# POWER_SHEET.net
KiCad netlist of a schematic drawn in Altium Designer
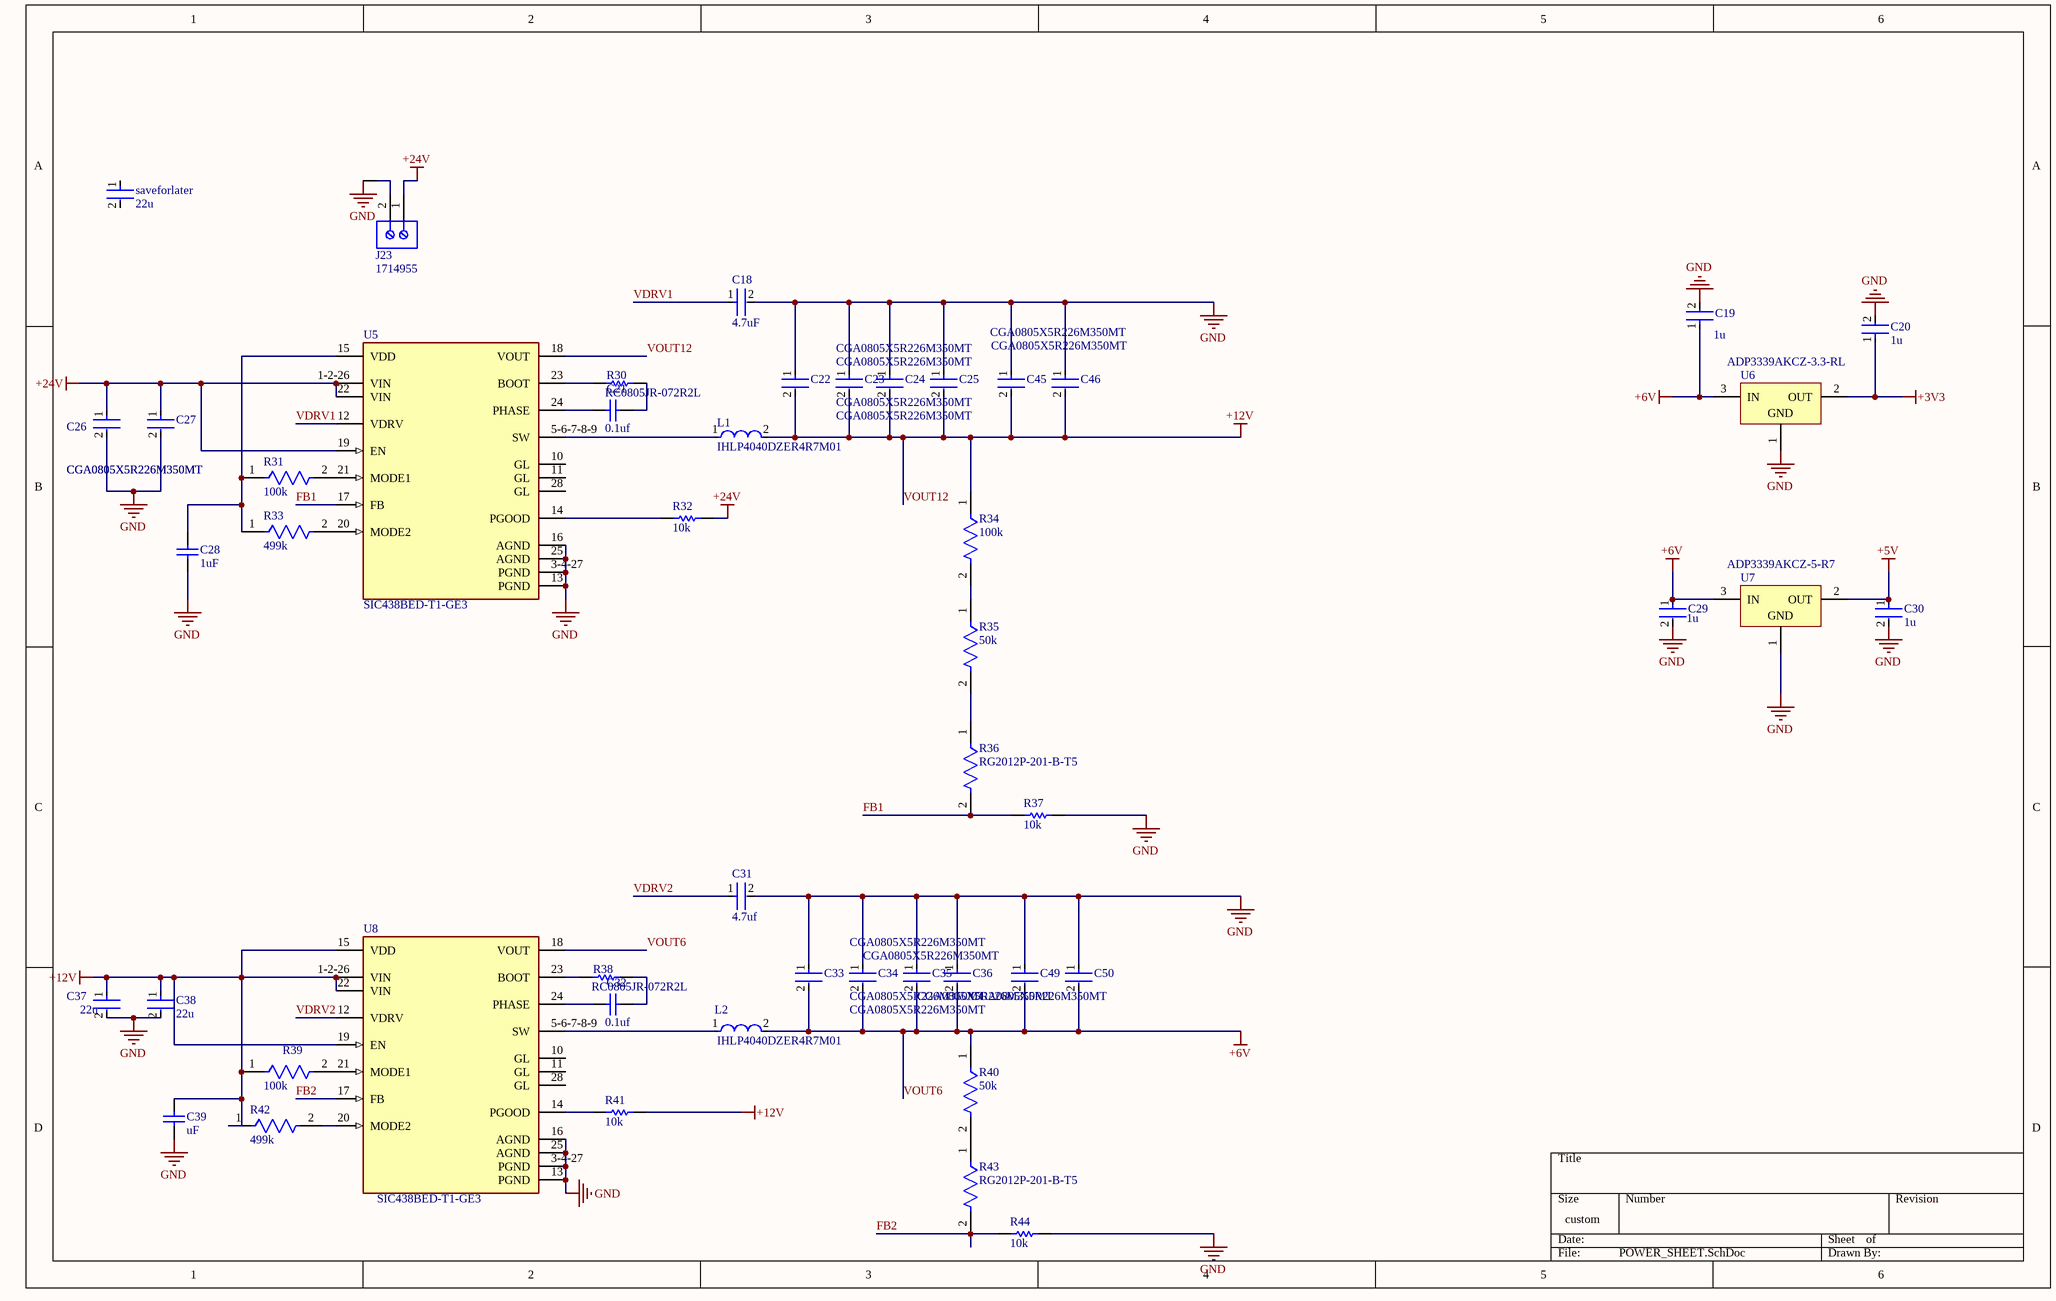
[diagram p0: POWER_SHEET.SchDoc]

(export (version "E")
  (design (tool "Eeschema 10.0.6"))
  (components
    (comp (ref "C18")
      (value "4.7uF")
      (footprint "FP-CL21-IPC_A")
      (description "CL21 Series 0805 4.7uF 25V ±10% Tolerance X5R Multilayer Ceramic Chip Capacitor")
      (fields (field (name "TOLERANCE") "10%"))
      (libsource (lib "Altium Content Vault") (part "b4654b650e69147ec39a6b967a45e02"))
    )
    (comp (ref "C19")
      (value "1u")
      (footprint "FP-CL21-IPC_A")
      (description "CL21 Series 0805 1uF 16V ±10% Tolerance X7R Multilayer Ceramic Chip Capacitor")
      (fields (field (name "TOLERANCE") "10%") (field (name "VOLTAGE") "16V"))
      (libsource (lib "Altium Content Vault") (part "b4654b650e69147ec39a6b967a45e02"))
    )
    (comp (ref "C20")
      (value "1u")
      (footprint "FP-CL21-IPC_A")
      (description "CL21 Series 0805 1uF 16V ±10% Tolerance X7R Multilayer Ceramic Chip Capacitor")
      (fields (field (name "TOLERANCE") "10%") (field (name "VOLTAGE") "16V"))
      (libsource (lib "Altium Content Vault") (part "b4654b650e69147ec39a6b967a45e02"))
    )
    (comp (ref "C21")
      (value "0.1uf")
      (footprint "CAPC2013X94X50LL20T25")
      (fields
        (field (name "MANUFACTURER") "AVX Interconnect / Elco")
        (field (name "PART NUMBER") "08055A6R0CAT2A")
      )
      (libsource (lib "Altium Content Vault") (part "CAP"))
    )
    (comp (ref "C22")
      (value "CGA0805X5R226M350MT")
      (footprint "FP-GRM21B-0_2-e0_2_0_7-IPC_A")
      (description "Chip Multilayer Ceramic Capacitors for General Purpose, 0805, 100uF, X5R, 15%, 20%, 6.3V")
      (fields (field (name "TOLERANCE") "20%"))
      (libsource (lib "Altium Content Vault") (part "b4654b650e69147ec39a6b967a45e02"))
    )
    (comp (ref "C23")
      (value "CGA0805X5R226M350MT")
      (footprint "FP-GRM21B-0_2-e0_2_0_7-IPC_A")
      (description "Chip Multilayer Ceramic Capacitors for General Purpose, 0805, 100uF, X5R, 15%, 20%, 6.3V")
      (fields (field (name "TOLERANCE") "20%"))
      (libsource (lib "Altium Content Vault") (part "b4654b650e69147ec39a6b967a45e02"))
    )
    (comp (ref "C24")
      (value "CGA0805X5R226M350MT")
      (footprint "FP-GRM21B-0_2-e0_2_0_7-IPC_A")
      (description "Chip Multilayer Ceramic Capacitors for General Purpose, 0805, 100uF, X5R, 15%, 20%, 6.3V")
      (fields (field (name "TOLERANCE") "20%"))
      (libsource (lib "Altium Content Vault") (part "b4654b650e69147ec39a6b967a45e02"))
    )
    (comp (ref "C25")
      (value "CGA0805X5R226M350MT")
      (footprint "FP-GRM21B-0_2-e0_2_0_7-IPC_A")
      (description "Chip Multilayer Ceramic Capacitors for General Purpose, 0805, 100uF, X5R, 15%, 20%, 6.3V")
      (fields (field (name "TOLERANCE") "20%"))
      (libsource (lib "Altium Content Vault") (part "b4654b650e69147ec39a6b967a45e02"))
    )
    (comp (ref "C26")
      (value "CGA0805X5R226M350MT")
      (footprint "FP-GRM21B-0_2-e0_2_0_7-IPC_A")
      (description "Chip Multilayer Ceramic Capacitors for General Purpose, 0805, 100uF, X5R, 15%, 20%, 6.3V")
      (fields (field (name "TOLERANCE") "20%"))
      (libsource (lib "Altium Content Vault") (part "b4654b650e69147ec39a6b967a45e02"))
    )
    (comp (ref "C27")
      (value "CGA0805X5R226M350MT")
      (footprint "FP-GRM21B-0_2-e0_2_0_7-IPC_A")
      (description "Chip Multilayer Ceramic Capacitors for General Purpose, 0805, 100uF, X5R, 15%, 20%, 6.3V")
      (fields (field (name "TOLERANCE") "20%"))
      (libsource (lib "Altium Content Vault") (part "b4654b650e69147ec39a6b967a45e02"))
    )
    (comp (ref "C28")
      (value "1uF")
      (footprint "CAPC2013X94X50ML25T25")
      (fields
        (field (name "MANUFACTURER") "AVX Interconnect / Elco")
        (field (name "PART NUMBER") "LD055C224KAB2A")
      )
      (libsource (lib "Altium Content Vault") (part "CAP"))
    )
    (comp (ref "C29")
      (value "1u")
      (footprint "FP-CL21-IPC_A")
      (description "CL21 Series 0805 1uF 16V ±10% Tolerance X7R Multilayer Ceramic Chip Capacitor")
      (fields (field (name "TOLERANCE") "10%") (field (name "VOLTAGE") "16V"))
      (libsource (lib "Altium Content Vault") (part "b4654b650e69147ec39a6b967a45e02"))
    )
    (comp (ref "C30")
      (value "1u")
      (footprint "FP-CL21-IPC_A")
      (description "CL21 Series 0805 1uF 16V ±10% Tolerance X7R Multilayer Ceramic Chip Capacitor")
      (fields (field (name "TOLERANCE") "10%") (field (name "VOLTAGE") "16V"))
      (libsource (lib "Altium Content Vault") (part "b4654b650e69147ec39a6b967a45e02"))
    )
    (comp (ref "C31")
      (value "4.7uf")
      (footprint "FP-CL21-IPC_A")
      (description "CL21 Series 0805 4.7uF 25V ±10% Tolerance X5R Multilayer Ceramic Chip Capacitor")
      (fields (field (name "TOLERANCE") "10%"))
      (libsource (lib "Altium Content Vault") (part "b4654b650e69147ec39a6b967a45e02"))
    )
    (comp (ref "C32")
      (value "0.1uf")
      (footprint "CAPC2013X94X50LL20T25")
      (fields
        (field (name "MANUFACTURER") "AVX Interconnect / Elco")
        (field (name "PART NUMBER") "08055A6R0CAT2A")
      )
      (libsource (lib "Altium Content Vault") (part "CAP"))
    )
    (comp (ref "C33")
      (value "CGA0805X5R226M350MT")
      (footprint "FP-GRM21B-0_2-e0_2_0_7-IPC_A")
      (description "Chip Multilayer Ceramic Capacitors for General Purpose, 0805, 100uF, X5R, 15%, 20%, 6.3V")
      (fields (field (name "TOLERANCE") "20%"))
      (libsource (lib "Altium Content Vault") (part "b4654b650e69147ec39a6b967a45e02"))
    )
    (comp (ref "C34")
      (value "CGA0805X5R226M350MT")
      (footprint "FP-GRM21B-0_2-e0_2_0_7-IPC_A")
      (description "Chip Multilayer Ceramic Capacitors for General Purpose, 0805, 100uF, X5R, 15%, 20%, 6.3V")
      (fields (field (name "TOLERANCE") "20%"))
      (libsource (lib "Altium Content Vault") (part "b4654b650e69147ec39a6b967a45e02"))
    )
    (comp (ref "C35")
      (value "CGA0805X5R226M350MT")
      (footprint "FP-GRM21B-0_2-e0_2_0_7-IPC_A")
      (description "Chip Multilayer Ceramic Capacitors for General Purpose, 0805, 100uF, X5R, 15%, 20%, 6.3V")
      (fields (field (name "TOLERANCE") "20%"))
      (libsource (lib "Altium Content Vault") (part "b4654b650e69147ec39a6b967a45e02"))
    )
    (comp (ref "C36")
      (value "CGA0805X5R226M350MT")
      (footprint "FP-GRM21B-0_2-e0_2_0_7-IPC_A")
      (description "Chip Multilayer Ceramic Capacitors for General Purpose, 0805, 100uF, X5R, 15%, 20%, 6.3V")
      (fields (field (name "TOLERANCE") "20%"))
      (libsource (lib "Altium Content Vault") (part "b4654b650e69147ec39a6b967a45e02"))
    )
    (comp (ref "C37")
      (value "22u")
      (footprint "FP-CL21-IPC_C")
      (description "CL21 Series 0805 22uF 25V ±20% Tolerance X5R Multilayer Ceramic Chip Capacitor")
      (libsource (lib "Altium Content Vault") (part "b4654b650e69147ec39a6b967a45e02"))
    )
    (comp (ref "C38")
      (value "22u")
      (footprint "FP-CL21-IPC_C")
      (description "CL21 Series 0805 22uF 25V ±20% Tolerance X5R Multilayer Ceramic Chip Capacitor")
      (libsource (lib "Altium Content Vault") (part "b4654b650e69147ec39a6b967a45e02"))
    )
    (comp (ref "C39")
      (value "uF")
      (footprint "CAPC2013X94X50ML25T25")
      (fields
        (field (name "MANUFACTURER") "AVX Interconnect / Elco")
        (field (name "PART NUMBER") "LD055C224KAB2A")
      )
      (libsource (lib "Altium Content Vault") (part "CAP"))
    )
    (comp (ref "C45")
      (value "CGA0805X5R226M350MT")
      (footprint "FP-GRM21B-0_2-e0_2_0_7-IPC_A")
      (description "Chip Multilayer Ceramic Capacitors for General Purpose, 0805, 100uF, X5R, 15%, 20%, 6.3V")
      (fields (field (name "TOLERANCE") "20%"))
      (libsource (lib "Altium Content Vault") (part "b4654b650e69147ec39a6b967a45e02"))
    )
    (comp (ref "C46")
      (value "CGA0805X5R226M350MT")
      (footprint "FP-GRM21B-0_2-e0_2_0_7-IPC_A")
      (description "Chip Multilayer Ceramic Capacitors for General Purpose, 0805, 100uF, X5R, 15%, 20%, 6.3V")
      (fields (field (name "TOLERANCE") "20%"))
      (libsource (lib "Altium Content Vault") (part "b4654b650e69147ec39a6b967a45e02"))
    )
    (comp (ref "C49")
      (value "CGA0805X5R226M350MT")
      (footprint "FP-GRM21B-0_2-e0_2_0_7-IPC_A")
      (description "Chip Multilayer Ceramic Capacitors for General Purpose, 0805, 100uF, X5R, 15%, 20%, 6.3V")
      (fields (field (name "TOLERANCE") "20%"))
      (libsource (lib "Altium Content Vault") (part "b4654b650e69147ec39a6b967a45e02"))
    )
    (comp (ref "C50")
      (value "CGA0805X5R226M350MT")
      (footprint "FP-GRM21B-0_2-e0_2_0_7-IPC_A")
      (description "Chip Multilayer Ceramic Capacitors for General Purpose, 0805, 100uF, X5R, 15%, 20%, 6.3V")
      (fields (field (name "TOLERANCE") "20%"))
      (libsource (lib "Altium Content Vault") (part "b4654b650e69147ec39a6b967a45e02"))
    )
    (comp (ref "J23")
      (value "1714955")
      (footprint "PHOE-1714955_V")
      (description "PC Terminal Block, Pitch 6.35 mm, 1 x 2 Position, Height 21.5 mm, Tail Lenght 5.1 mm, RoHS, Bulk")
      (fields (field (name "MANUFACTURER") "Phoenix Contact"))
      (libsource (lib "Altium Content Vault") (part "CN-1P-F-TB2"))
    )
    (comp (ref "L1")
      (value "IHLP4040DZER4R7M01")
      (footprint "FP-IHLP-4040DZ-FP_3_124x3-MFG")
      (description "Commercial Inductors, High Saturation Series 4.7uH 9.5A 16.5mΩ 20%")
      (fields (field (name "TOLERANCE") "20%"))
      (libsource (lib "Altium Content Vault") (part "725321dda6339637d4d059423bc1c3c"))
    )
    (comp (ref "L2")
      (value "IHLP4040DZER4R7M01")
      (footprint "FP-IHLP-4040DZ-FP_3_124x3-MFG")
      (description "Commercial Inductors, High Saturation Series 4.7uH 9.5A 16.5mΩ 20%")
      (fields (field (name "TOLERANCE") "20%"))
      (libsource (lib "Altium Content Vault") (part "725321dda6339637d4d059423bc1c3c"))
    )
    (comp (ref "R30")
      (value "RC0805JR-072R2L")
      (footprint "RESC2013X60X35LL10T20")
      (fields (field (name "MANUFACTURER") "Yageo"))
      (libsource (lib "Altium Content Vault") (part "RES"))
    )
    (comp (ref "R31")
      (value "100k")
      (footprint "FP-ESR10-MFG")
      (description "100kΩ ±5% 0.4W 0805 Anti-Surge Chip Resistor AEC-Q200")
      (fields (field (name "TOLERANCE") "5%"))
      (libsource (lib "Altium Content Vault") (part "1029c3af85768c4190bb7ad29bc67b5"))
    )
    (comp (ref "R32")
      (value "10k")
      (footprint "RESC2013X60X40LL20T25_A")
      (fields (field (name "TOLERANCE") "0.1%") (field (name "MANUFACTURER") "Panasonic"))
      (libsource (lib "Altium Content Vault") (part "RES-2"))
    )
    (comp (ref "R33")
      (value "499k")
      (footprint "FP-RT0805-MFG")
      (description "RES SMD 332K OHM 1% 1/8W 0805")
      (fields
        (field (name "OCTOPART") "https://octopart.com/rt0805fre07332kl-yageo-1277672")
        (field (name "TOLERANCE") "0.0001")
      )
      (libsource (lib "Altium Content Vault") (part "1029c3af85768c4190bb7ad29bc67b5"))
    )
    (comp (ref "R34")
      (value "100k")
      (footprint "FP-ESR10-MFG")
      (description "100kΩ ±5% 0.4W 0805 Anti-Surge Chip Resistor AEC-Q200")
      (fields (field (name "TOLERANCE") "5%"))
      (libsource (lib "Altium Content Vault") (part "1029c3af85768c4190bb7ad29bc67b5"))
    )
    (comp (ref "R35")
      (value "50k")
      (footprint "FP-PNM0805-MFG")
      (description "RES SMD 50K OHM 0.1% 1/5W 0805")
      (fields (field (name "TOLERANCE") "0.1%"))
      (libsource (lib "Altium Content Vault") (part "1029c3af85768c4190bb7ad29bc67b5"))
    )
    (comp (ref "R36")
      (value "RG2012P-201-B-T5")
      (footprint "FP-RG2012-IPC_A")
      (description "Automotive Metal Thin Film Chip Resistor, 0805, 200Ω, 0.1%, 25ppm/°C, 0.125W, 150V")
      (fields (field (name "TOLERANCE") "0.1%"))
      (libsource (lib "Altium Content Vault") (part "1029c3af85768c4190bb7ad29bc67b5"))
    )
    (comp (ref "R37")
      (value "10k")
      (footprint "RESC2013X60X40LL20T25_A")
      (fields (field (name "TOLERANCE") "0.1%") (field (name "MANUFACTURER") "Panasonic"))
      (libsource (lib "Altium Content Vault") (part "RES-2"))
    )
    (comp (ref "R38")
      (value "RC0805JR-072R2L")
      (footprint "RESC2013X60X35LL10T20")
      (fields (field (name "MANUFACTURER") "Yageo"))
      (libsource (lib "Altium Content Vault") (part "RES"))
    )
    (comp (ref "R39")
      (value "100k")
      (footprint "FP-ESR10-MFG")
      (description "100kΩ ±5% 0.4W 0805 Anti-Surge Chip Resistor AEC-Q200")
      (fields (field (name "TOLERANCE") "5%"))
      (libsource (lib "Altium Content Vault") (part "1029c3af85768c4190bb7ad29bc67b5"))
    )
    (comp (ref "R40")
      (value "50k")
      (footprint "FP-PNM0805-MFG")
      (description "RES SMD 50K OHM 0.1% 1/5W 0805")
      (fields (field (name "TOLERANCE") "0.1%"))
      (libsource (lib "Altium Content Vault") (part "1029c3af85768c4190bb7ad29bc67b5"))
    )
    (comp (ref "R41")
      (value "10k")
      (footprint "RESC2013X60X40LL20T25_A")
      (fields (field (name "TOLERANCE") "0.1%") (field (name "MANUFACTURER") "Panasonic"))
      (libsource (lib "Altium Content Vault") (part "RES-2"))
    )
    (comp (ref "R42")
      (value "499k")
      (footprint "FP-RT0805-MFG")
      (description "RES SMD 332K OHM 1% 1/8W 0805")
      (fields
        (field (name "OCTOPART") "https://octopart.com/rt0805fre07332kl-yageo-1277672")
        (field (name "TOLERANCE") "0.0001")
      )
      (libsource (lib "Altium Content Vault") (part "1029c3af85768c4190bb7ad29bc67b5"))
    )
    (comp (ref "R43")
      (value "RG2012P-201-B-T5")
      (footprint "FP-RG2012-IPC_A")
      (description "Automotive Metal Thin Film Chip Resistor, 0805, 200Ω, 0.1%, 25ppm/°C, 0.125W, 150V")
      (fields (field (name "TOLERANCE") "0.1%"))
      (libsource (lib "Altium Content Vault") (part "1029c3af85768c4190bb7ad29bc67b5"))
    )
    (comp (ref "R44")
      (value "10k")
      (footprint "RESC2013X60X40LL20T25_A")
      (fields (field (name "TOLERANCE") "0.1%") (field (name "MANUFACTURER") "Panasonic"))
      (libsource (lib "Altium Content Vault") (part "RES-2"))
    )
    (comp (ref "saveforlater")
      (value "22u")
      (footprint "FP-CL21-IPC_C")
      (description "CL21 Series 0805 22uF 25V ±20% Tolerance X5R Multilayer Ceramic Chip Capacitor")
      (libsource (lib "Altium Content Vault") (part "b4654b650e69147ec39a6b967a45e02"))
    )
    (comp (ref "U5")
      (value "SIC438BED-T1-GE3")
      (footprint "FP-T22-0442-MFG")
      (libsource (lib "Altium Content Vault") (part "ab0672d4ef5f671f4783a9619e06a30"))
    )
    (comp (ref "U6")
      (value "ADP3339AKCZ-3.3-RL")
      (footprint "ADI-KC-3_N")
      (fields (field (name "MANUFACTURER") "Analog Devices"))
      (libsource (lib "Altium Content Vault") (part "ADI-ADP3339-KC-3"))
    )
    (comp (ref "U7")
      (value "ADP3339AKCZ-5-R7")
      (footprint "ADI-KC-3_N")
      (fields (field (name "MANUFACTURER") "Analog Devices"))
      (libsource (lib "Altium Content Vault") (part "ADI-ADP3339-KC-3"))
    )
    (comp (ref "U8")
      (value "SIC438BED-T1-GE3")
      (footprint "FP-T22-0442-MFG")
      (libsource (lib "Altium Content Vault") (part "ab0672d4ef5f671f4783a9619e06a30"))
    )
  )
  (nets
    (net (code "1") (name "+3V3") (class "Default")
      (node (ref "C20") (pin "1") (pinfunction "1_1") (pintype "passive"))
      (node (ref "U6") (pin "2") (pinfunction "OUT_2") (pintype "power_in"))
    )
    (net (code "2") (name "+5V") (class "Default")
      (node (ref "C30") (pin "1") (pinfunction "1_1") (pintype "passive"))
      (node (ref "U7") (pin "2") (pinfunction "OUT_2") (pintype "power_in"))
    )
    (net (code "3") (name "+6V") (class "Default")
      (node (ref "C19") (pin "1") (pinfunction "1_1") (pintype "passive"))
      (node (ref "C29") (pin "1") (pinfunction "1_1") (pintype "passive"))
      (node (ref "C33") (pin "2") (pinfunction "2_2") (pintype "passive"))
      (node (ref "C34") (pin "2") (pinfunction "2_2") (pintype "passive"))
      (node (ref "C35") (pin "2") (pinfunction "2_2") (pintype "passive"))
      (node (ref "C36") (pin "2") (pinfunction "2_2") (pintype "passive"))
      (node (ref "C49") (pin "2") (pinfunction "2_2") (pintype "passive"))
      (node (ref "C50") (pin "2") (pinfunction "2_2") (pintype "passive"))
      (node (ref "L2") (pin "2") (pinfunction "2_2") (pintype "passive"))
      (node (ref "R40") (pin "1") (pinfunction "1_1") (pintype "passive"))
      (node (ref "U6") (pin "3") (pinfunction "IN_3") (pintype "power_in"))
      (node (ref "U7") (pin "3") (pinfunction "IN_3") (pintype "power_in"))
      (node (ref "U8") (pin "18") (pinfunction "VOUT_18") (pintype "passive"))
    )
    (net (code "4") (name "+12V") (class "Default")
      (node (ref "C22") (pin "2") (pinfunction "2_2") (pintype "passive"))
      (node (ref "C23") (pin "2") (pinfunction "2_2") (pintype "passive"))
      (node (ref "C24") (pin "2") (pinfunction "2_2") (pintype "passive"))
      (node (ref "C25") (pin "2") (pinfunction "2_2") (pintype "passive"))
      (node (ref "C37") (pin "1") (pinfunction "1_1") (pintype "passive"))
      (node (ref "C38") (pin "1") (pinfunction "1_1") (pintype "passive"))
      (node (ref "C39") (pin "2") (pinfunction "2_2") (pintype "passive"))
      (node (ref "C45") (pin "2") (pinfunction "2_2") (pintype "passive"))
      (node (ref "C46") (pin "2") (pinfunction "2_2") (pintype "passive"))
      (node (ref "L1") (pin "2") (pinfunction "2_2") (pintype "passive"))
      (node (ref "R34") (pin "1") (pinfunction "1_1") (pintype "passive"))
      (node (ref "R39") (pin "1") (pinfunction "1_1") (pintype "passive"))
      (node (ref "R41") (pin "2") (pinfunction "2_2") (pintype "passive"))
      (node (ref "R42") (pin "1") (pinfunction "1_1") (pintype "passive"))
      (node (ref "U5") (pin "18") (pinfunction "VOUT_18") (pintype "passive"))
      (node (ref "U8") (pin "1-2-26") (pinfunction "VIN_1-2-26") (pintype "power_in"))
      (node (ref "U8") (pin "15") (pinfunction "VDD_15") (pintype "power_in"))
      (node (ref "U8") (pin "19") (pinfunction "EN_19") (pintype "input"))
      (node (ref "U8") (pin "22") (pinfunction "VIN_22") (pintype "power_in"))
    )
    (net (code "5") (name "+24V") (class "Default")
      (node (ref "C26") (pin "1") (pinfunction "1_1") (pintype "passive"))
      (node (ref "C27") (pin "1") (pinfunction "1_1") (pintype "passive"))
      (node (ref "J23") (pin "1") (pinfunction "1_1") (pintype "passive"))
      (node (ref "R32") (pin "2") (pinfunction "2_2") (pintype "passive"))
      (node (ref "U5") (pin "1-2-26") (pinfunction "VIN_1-2-26") (pintype "power_in"))
      (node (ref "U5") (pin "19") (pinfunction "EN_19") (pintype "input"))
      (node (ref "U5") (pin "22") (pinfunction "VIN_22") (pintype "power_in"))
    )
    (net (code "6") (name "/FB1") (class "Default")
      (node (ref "R36") (pin "2") (pinfunction "2_2") (pintype "passive"))
      (node (ref "R37") (pin "1") (pinfunction "1_1") (pintype "passive"))
      (node (ref "U5") (pin "17") (pinfunction "FB_17") (pintype "input"))
    )
    (net (code "7") (name "/FB2") (class "Default")
      (node (ref "R43") (pin "2") (pinfunction "2_2") (pintype "passive"))
      (node (ref "R44") (pin "1") (pinfunction "1_1") (pintype "passive"))
      (node (ref "U8") (pin "17") (pinfunction "FB_17") (pintype "input"))
    )
    (net (code "8") (name "/VDRV1") (class "Default")
      (node (ref "C18") (pin "1") (pinfunction "1_1") (pintype "passive"))
      (node (ref "U5") (pin "12") (pinfunction "VDRV_12") (pintype "passive"))
    )
    (net (code "9") (name "/VDRV2") (class "Default")
      (node (ref "C31") (pin "1") (pinfunction "1_1") (pintype "passive"))
      (node (ref "U8") (pin "12") (pinfunction "VDRV_12") (pintype "passive"))
    )
    (net (code "10") (name "GND") (class "Default")
      (node (ref "C18") (pin "2") (pinfunction "2_2") (pintype "passive"))
      (node (ref "C19") (pin "2") (pinfunction "2_2") (pintype "passive"))
      (node (ref "C20") (pin "2") (pinfunction "2_2") (pintype "passive"))
      (node (ref "C22") (pin "1") (pinfunction "1_1") (pintype "passive"))
      (node (ref "C23") (pin "1") (pinfunction "1_1") (pintype "passive"))
      (node (ref "C24") (pin "1") (pinfunction "1_1") (pintype "passive"))
      (node (ref "C25") (pin "1") (pinfunction "1_1") (pintype "passive"))
      (node (ref "C26") (pin "2") (pinfunction "2_2") (pintype "passive"))
      (node (ref "C27") (pin "2") (pinfunction "2_2") (pintype "passive"))
      (node (ref "C28") (pin "1") (pinfunction "1_1") (pintype "passive"))
      (node (ref "C29") (pin "2") (pinfunction "2_2") (pintype "passive"))
      (node (ref "C30") (pin "2") (pinfunction "2_2") (pintype "passive"))
      (node (ref "C31") (pin "2") (pinfunction "2_2") (pintype "passive"))
      (node (ref "C33") (pin "1") (pinfunction "1_1") (pintype "passive"))
      (node (ref "C34") (pin "1") (pinfunction "1_1") (pintype "passive"))
      (node (ref "C35") (pin "1") (pinfunction "1_1") (pintype "passive"))
      (node (ref "C36") (pin "1") (pinfunction "1_1") (pintype "passive"))
      (node (ref "C37") (pin "2") (pinfunction "2_2") (pintype "passive"))
      (node (ref "C38") (pin "2") (pinfunction "2_2") (pintype "passive"))
      (node (ref "C39") (pin "1") (pinfunction "1_1") (pintype "passive"))
      (node (ref "C45") (pin "1") (pinfunction "1_1") (pintype "passive"))
      (node (ref "C46") (pin "1") (pinfunction "1_1") (pintype "passive"))
      (node (ref "C49") (pin "1") (pinfunction "1_1") (pintype "passive"))
      (node (ref "C50") (pin "1") (pinfunction "1_1") (pintype "passive"))
      (node (ref "J23") (pin "2") (pinfunction "2_2") (pintype "passive"))
      (node (ref "R37") (pin "2") (pinfunction "2_2") (pintype "passive"))
      (node (ref "R44") (pin "2") (pinfunction "2_2") (pintype "passive"))
      (node (ref "U5") (pin "13") (pinfunction "PGND_13") (pintype "power_in"))
      (node (ref "U5") (pin "16") (pinfunction "AGND_16") (pintype "power_in"))
      (node (ref "U5") (pin "25") (pinfunction "AGND_25") (pintype "power_in"))
      (node (ref "U5") (pin "3-4-27") (pinfunction "PGND_3-4-27") (pintype "power_in"))
      (node (ref "U6") (pin "1") (pinfunction "GND_1") (pintype "power_in"))
      (node (ref "U7") (pin "1") (pinfunction "GND_1") (pintype "power_in"))
      (node (ref "U8") (pin "13") (pinfunction "PGND_13") (pintype "power_in"))
      (node (ref "U8") (pin "16") (pinfunction "AGND_16") (pintype "power_in"))
      (node (ref "U8") (pin "25") (pinfunction "AGND_25") (pintype "power_in"))
      (node (ref "U8") (pin "3-4-27") (pinfunction "PGND_3-4-27") (pintype "power_in"))
    )
    (net (code "11") (name "Net-(C21-Pad2)") (class "Default")
      (node (ref "C21") (pin "2") (pinfunction "2_2") (pintype "passive"))
      (node (ref "R30") (pin "2") (pinfunction "2_2") (pintype "passive"))
    )
    (net (code "12") (name "Net-(C32-Pad2)") (class "Default")
      (node (ref "C32") (pin "2") (pinfunction "2_2") (pintype "passive"))
      (node (ref "R38") (pin "2") (pinfunction "2_2") (pintype "passive"))
    )
    (net (code "13") (name "Net-(R34-Pad2)") (class "Default")
      (node (ref "R34") (pin "2") (pinfunction "2_2") (pintype "passive"))
      (node (ref "R35") (pin "1") (pinfunction "1_1") (pintype "passive"))
    )
    (net (code "14") (name "Net-(R35-Pad2)") (class "Default")
      (node (ref "R35") (pin "2") (pinfunction "2_2") (pintype "passive"))
      (node (ref "R36") (pin "1") (pinfunction "1_1") (pintype "passive"))
    )
    (net (code "15") (name "Net-(R40-Pad2)") (class "Default")
      (node (ref "R40") (pin "2") (pinfunction "2_2") (pintype "passive"))
      (node (ref "R43") (pin "1") (pinfunction "1_1") (pintype "passive"))
    )
    (net (code "16") (name "Net-(U5-BOOT)") (class "Default")
      (node (ref "R30") (pin "1") (pinfunction "1_1") (pintype "passive"))
      (node (ref "U5") (pin "23") (pinfunction "BOOT_23") (pintype "passive"))
    )
    (net (code "17") (name "Net-(U5-MODE1)") (class "Default")
      (node (ref "R31") (pin "2") (pinfunction "2_2") (pintype "passive"))
      (node (ref "U5") (pin "21") (pinfunction "MODE1_21") (pintype "input"))
    )
    (net (code "18") (name "Net-(U5-MODE2)") (class "Default")
      (node (ref "R33") (pin "2") (pinfunction "2_2") (pintype "passive"))
      (node (ref "U5") (pin "20") (pinfunction "MODE2_20") (pintype "input"))
    )
    (net (code "19") (name "Net-(U5-PGOOD)") (class "Default")
      (node (ref "R32") (pin "1") (pinfunction "1_1") (pintype "passive"))
      (node (ref "U5") (pin "14") (pinfunction "PGOOD_14") (pintype "open_collector"))
    )
    (net (code "20") (name "Net-(U5-PHASE)") (class "Default")
      (node (ref "C21") (pin "1") (pinfunction "1_1") (pintype "passive"))
      (node (ref "U5") (pin "24") (pinfunction "PHASE_24") (pintype "passive"))
    )
    (net (code "21") (name "Net-(U5-SW)") (class "Default")
      (node (ref "L1") (pin "1") (pinfunction "1_1") (pintype "passive"))
      (node (ref "U5") (pin "5-6-7-8-9") (pinfunction "SW_5-6-7-8-9") (pintype "passive"))
    )
    (net (code "22") (name "Net-(U5-VDD)") (class "Default")
      (node (ref "C28") (pin "2") (pinfunction "2_2") (pintype "passive"))
      (node (ref "R31") (pin "1") (pinfunction "1_1") (pintype "passive"))
      (node (ref "R33") (pin "1") (pinfunction "1_1") (pintype "passive"))
      (node (ref "U5") (pin "15") (pinfunction "VDD_15") (pintype "power_in"))
    )
    (net (code "23") (name "Net-(U8-BOOT)") (class "Default")
      (node (ref "R38") (pin "1") (pinfunction "1_1") (pintype "passive"))
      (node (ref "U8") (pin "23") (pinfunction "BOOT_23") (pintype "passive"))
    )
    (net (code "24") (name "Net-(U8-MODE1)") (class "Default")
      (node (ref "R39") (pin "2") (pinfunction "2_2") (pintype "passive"))
      (node (ref "U8") (pin "21") (pinfunction "MODE1_21") (pintype "input"))
    )
    (net (code "25") (name "Net-(U8-MODE2)") (class "Default")
      (node (ref "R42") (pin "2") (pinfunction "2_2") (pintype "passive"))
      (node (ref "U8") (pin "20") (pinfunction "MODE2_20") (pintype "input"))
    )
    (net (code "26") (name "Net-(U8-PGOOD)") (class "Default")
      (node (ref "R41") (pin "1") (pinfunction "1_1") (pintype "passive"))
      (node (ref "U8") (pin "14") (pinfunction "PGOOD_14") (pintype "open_collector"))
    )
    (net (code "27") (name "Net-(U8-PHASE)") (class "Default")
      (node (ref "C32") (pin "1") (pinfunction "1_1") (pintype "passive"))
      (node (ref "U8") (pin "24") (pinfunction "PHASE_24") (pintype "passive"))
    )
    (net (code "28") (name "Net-(U8-SW)") (class "Default")
      (node (ref "L2") (pin "1") (pinfunction "1_1") (pintype "passive"))
      (node (ref "U8") (pin "5-6-7-8-9") (pinfunction "SW_5-6-7-8-9") (pintype "passive"))
    )
    (net (code "29") (name "unconnected-(U5-GL-Pad10)") (class "Default")
      (node (ref "U5") (pin "10") (pinfunction "GL_10") (pintype "passive"))
    )
    (net (code "30") (name "unconnected-(U5-GL-Pad11)") (class "Default")
      (node (ref "U5") (pin "11") (pinfunction "GL_11") (pintype "passive"))
    )
    (net (code "31") (name "unconnected-(U5-GL-Pad28)") (class "Default")
      (node (ref "U5") (pin "28") (pinfunction "GL_28") (pintype "passive"))
    )
    (net (code "32") (name "unconnected-(U8-GL-Pad10)") (class "Default")
      (node (ref "U8") (pin "10") (pinfunction "GL_10") (pintype "passive"))
    )
    (net (code "33") (name "unconnected-(U8-GL-Pad11)") (class "Default")
      (node (ref "U8") (pin "11") (pinfunction "GL_11") (pintype "passive"))
    )
    (net (code "34") (name "unconnected-(U8-GL-Pad28)") (class "Default")
      (node (ref "U8") (pin "28") (pinfunction "GL_28") (pintype "passive"))
    )
    (net (code "35") (name "unconnected-(saveforlater-Pad1)") (class "Default")
      (node (ref "saveforlater") (pin "1") (pinfunction "1_1") (pintype "passive"))
    )
    (net (code "36") (name "unconnected-(saveforlater-Pad2)") (class "Default")
      (node (ref "saveforlater") (pin "2") (pinfunction "2_2") (pintype "passive"))
    )
  )
)
